# motor_ctrl_pw_v3.net
KiCad netlist of a schematic drawn in EAGLE
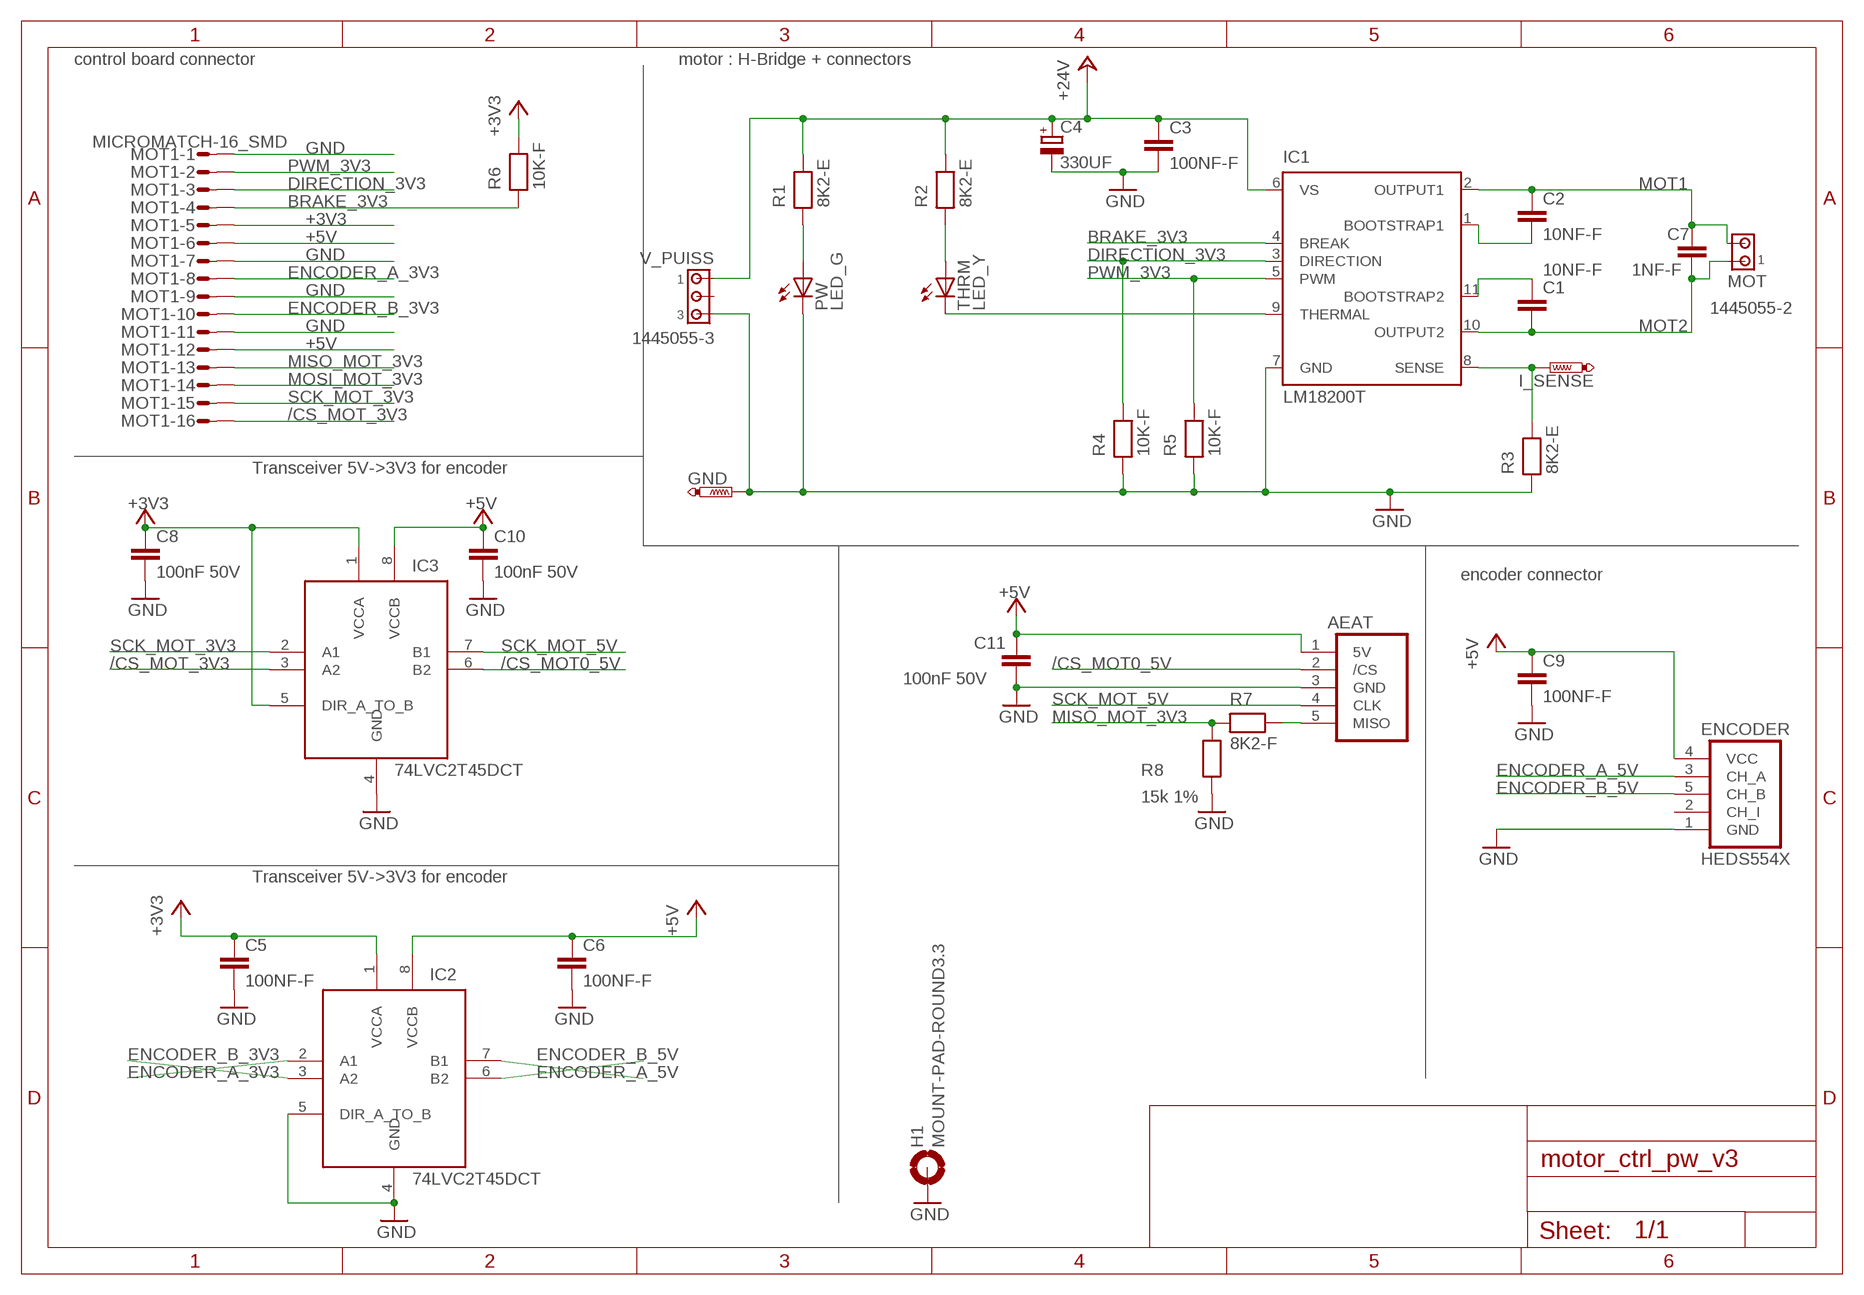
[diagram p0: schematic, sheet 1]

(export (version "E")
  (design (tool "Eeschema 10.0.6"))
  (components
    (comp (ref "AEAT")
      (value "AEAT-601X")
      (footprint "eagle-import:53047-05")
      (libsource (lib "eagle-import") (part "AEAT-601X"))
    )
    (comp (ref "C1")
      (value "10NF-F")
      (footprint "eagle-import:C0603")
      (libsource (lib "eagle-import") (part "10NF-F"))
    )
    (comp (ref "C2")
      (value "10NF-F")
      (footprint "eagle-import:C0603")
      (libsource (lib "eagle-import") (part "10NF-F"))
    )
    (comp (ref "C3")
      (value "100NF-F")
      (footprint "eagle-import:C0603")
      (libsource (lib "eagle-import") (part "100NF-F"))
    )
    (comp (ref "C4")
      (value "330UF")
      (footprint "eagle-import:PANASONIC_G")
      (fields (field (name "MANUFACTURER") "EEEFK1V331P"))
      (libsource (lib "eagle-import") (part "330UF"))
    )
    (comp (ref "C5")
      (value "100NF-F")
      (footprint "eagle-import:C0603")
      (libsource (lib "eagle-import") (part "100NF-F"))
    )
    (comp (ref "C6")
      (value "100NF-F")
      (footprint "eagle-import:C0603")
      (libsource (lib "eagle-import") (part "100NF-F"))
    )
    (comp (ref "C7")
      (value "1NF-F")
      (footprint "eagle-import:C0603")
      (libsource (lib "eagle-import") (part "1NF-F"))
    )
    (comp (ref "C8")
      (value "100nF 50V")
      (footprint "eagle-import:C0603")
      (libsource (lib "eagle-import") (part "100NF-F"))
    )
    (comp (ref "C9")
      (value "100NF-F")
      (footprint "eagle-import:C0603")
      (libsource (lib "eagle-import") (part "100NF-F"))
    )
    (comp (ref "C10")
      (value "100nF 50V")
      (footprint "eagle-import:C0603")
      (libsource (lib "eagle-import") (part "100NF-F"))
    )
    (comp (ref "C11")
      (value "100nF 50V")
      (footprint "eagle-import:C0603")
      (libsource (lib "eagle-import") (part "100NF-F"))
    )
    (comp (ref "ENCODER")
      (value "HEDS554X")
      (footprint "eagle-import:22-05-1052")
      (libsource (lib "eagle-import") (part "HEDS554X"))
    )
    (comp (ref "GND")
      (value "PTR1PAD1-13")
      (footprint "eagle-import:P1-13")
      (libsource (lib "eagle-import") (part "PTR1PAD1-13"))
    )
    (comp (ref "H1")
      (value "MOUNT-PAD-ROUND3.3")
      (footprint "eagle-import:3,3-PAD")
      (libsource (lib "eagle-import") (part "MOUNT-PAD-ROUND3.3"))
    )
    (comp (ref "IC1")
      (value "LM18200T")
      (footprint "eagle-import:TO-220-11")
      (libsource (lib "eagle-import") (part "LM18200T"))
    )
    (comp (ref "IC2")
      (value "74LVC2T45DCT")
      (footprint "eagle-import:SSOP8")
      (libsource (lib "eagle-import") (part "74LVC2T45DCT"))
    )
    (comp (ref "IC3")
      (value "74LVC2T45DCT")
      (footprint "eagle-import:SSOP8")
      (libsource (lib "eagle-import") (part "74LVC2T45DCT"))
    )
    (comp (ref "I_SENSE")
      (value "PTR1PAD1-13")
      (footprint "eagle-import:P1-13")
      (libsource (lib "eagle-import") (part "PTR1PAD1-13"))
    )
    (comp (ref "MOT")
      (value "1445055-2")
      (footprint "eagle-import:1445055-2")
      (libsource (lib "eagle-import") (part "1445055-2"))
    )
    (comp (ref "MOT1")
      (value "MICROMATCH-16_SMD")
      (footprint "eagle-import:MICROMATCH-16_SMD")
      (libsource (lib "eagle-import") (part "MICROMATCH-16_SMD"))
    )
    (comp (ref "PW")
      (value "LED_G")
      (footprint "eagle-import:CHIP-LED0805")
      (libsource (lib "eagle-import") (part "LED_G"))
    )
    (comp (ref "R1")
      (value "8K2-E")
      (footprint "eagle-import:R0805")
      (libsource (lib "eagle-import") (part "8K2-E"))
    )
    (comp (ref "R2")
      (value "8K2-E")
      (footprint "eagle-import:R0805")
      (libsource (lib "eagle-import") (part "8K2-E"))
    )
    (comp (ref "R3")
      (value "8K2-E")
      (footprint "eagle-import:R0805")
      (libsource (lib "eagle-import") (part "8K2-E"))
    )
    (comp (ref "R4")
      (value "10K-F")
      (footprint "eagle-import:R0603")
      (libsource (lib "eagle-import") (part "10K-F"))
    )
    (comp (ref "R5")
      (value "10K-F")
      (footprint "eagle-import:R0603")
      (libsource (lib "eagle-import") (part "10K-F"))
    )
    (comp (ref "R6")
      (value "10K-F")
      (footprint "eagle-import:R0603")
      (libsource (lib "eagle-import") (part "10K-F"))
    )
    (comp (ref "R7")
      (value "8K2-F")
      (footprint "eagle-import:R0603")
      (libsource (lib "eagle-import") (part "8K2-F"))
    )
    (comp (ref "R8")
      (value "15k 1%")
      (footprint "eagle-import:R0603")
      (libsource (lib "eagle-import") (part "15K-F"))
    )
    (comp (ref "THRM")
      (value "LED_Y")
      (footprint "eagle-import:CHIP-LED0805")
      (libsource (lib "eagle-import") (part "LED_Y"))
    )
    (comp (ref "V_PUISS")
      (value "1445055-3")
      (footprint "eagle-import:1445055-3")
      (libsource (lib "eagle-import") (part "1445055-3"))
    )
  )
  (nets
    (net (code "1") (name "+3V3") (class "Default")
      (node (ref "C5") (pin "1") (pinfunction "1_1") (pintype "passive"))
      (node (ref "C8") (pin "1") (pinfunction "1_1") (pintype "passive"))
      (node (ref "IC2") (pin "1") (pinfunction "VCCA_1") (pintype "power_in"))
      (node (ref "IC3") (pin "1") (pinfunction "VCCA_1") (pintype "power_in"))
      (node (ref "IC3") (pin "5") (pinfunction "DIR_A_TO_B_5") (pintype "bidirectional"))
      (node (ref "MOT1") (pin "5") (pinfunction "S_5") (pintype "passive"))
      (node (ref "R6") (pin "2") (pinfunction "2_2") (pintype "bidirectional"))
    )
    (net (code "2") (name "+5V") (class "Default")
      (node (ref "AEAT") (pin "1") (pinfunction "5V_1") (pintype "passive"))
      (node (ref "C10") (pin "1") (pinfunction "1_1") (pintype "passive"))
      (node (ref "C11") (pin "1") (pinfunction "1_1") (pintype "passive"))
      (node (ref "C6") (pin "1") (pinfunction "1_1") (pintype "passive"))
      (node (ref "C9") (pin "1") (pinfunction "1_1") (pintype "passive"))
      (node (ref "ENCODER") (pin "4") (pinfunction "VCC_4") (pintype "passive"))
      (node (ref "IC2") (pin "8") (pinfunction "VCCB_8") (pintype "power_in"))
      (node (ref "IC3") (pin "8") (pinfunction "VCCB_8") (pintype "power_in"))
      (node (ref "MOT1") (pin "12") (pinfunction "S_12") (pintype "passive"))
      (node (ref "MOT1") (pin "6") (pinfunction "S_6") (pintype "passive"))
    )
    (net (code "3") (name "+24V") (class "Default")
      (node (ref "C3") (pin "1") (pinfunction "1_1") (pintype "passive"))
      (node (ref "C4") (pin "+") (pinfunction "+_+") (pintype "passive"))
      (node (ref "IC1") (pin "6") (pinfunction "VS_6") (pintype "power_in"))
      (node (ref "R1") (pin "2") (pinfunction "2_2") (pintype "bidirectional"))
      (node (ref "R2") (pin "2") (pinfunction "2_2") (pintype "bidirectional"))
      (node (ref "V_PUISS") (pin "1") (pinfunction "1_1") (pintype "passive"))
    )
    (net (code "4") (name "/BRAKE_3V3") (class "Default")
      (node (ref "IC1") (pin "4") (pinfunction "BREAK_4") (pintype "input"))
      (node (ref "MOT1") (pin "4") (pinfunction "S_4") (pintype "passive"))
      (node (ref "R6") (pin "1") (pinfunction "1_1") (pintype "bidirectional"))
    )
    (net (code "5") (name "/DIRECTION_3V3") (class "Default")
      (node (ref "IC1") (pin "3") (pinfunction "DIRECTION_3") (pintype "input"))
      (node (ref "MOT1") (pin "3") (pinfunction "S_3") (pintype "passive"))
      (node (ref "R4") (pin "2") (pinfunction "2_2") (pintype "bidirectional"))
    )
    (net (code "6") (name "/ENCODER_A_3V3") (class "Default")
      (node (ref "IC2") (pin "2") (pinfunction "A1_2") (pintype "bidirectional"))
      (node (ref "MOT1") (pin "8") (pinfunction "S_8") (pintype "passive"))
    )
    (net (code "7") (name "/ENCODER_A_5V") (class "Default")
      (node (ref "ENCODER") (pin "3") (pinfunction "CH_A_3") (pintype "passive"))
      (node (ref "IC2") (pin "7") (pinfunction "B1_7") (pintype "bidirectional"))
    )
    (net (code "8") (name "/ENCODER_B_3V3") (class "Default")
      (node (ref "IC2") (pin "3") (pinfunction "A2_3") (pintype "bidirectional"))
      (node (ref "MOT1") (pin "10") (pinfunction "S_10") (pintype "passive"))
    )
    (net (code "9") (name "/ENCODER_B_5V") (class "Default")
      (node (ref "ENCODER") (pin "5") (pinfunction "CH_B_5") (pintype "passive"))
      (node (ref "IC2") (pin "6") (pinfunction "B2_6") (pintype "bidirectional"))
    )
    (net (code "10") (name "/MISO_MOT_3V3") (class "Default")
      (node (ref "MOT1") (pin "13") (pinfunction "S_13") (pintype "passive"))
      (node (ref "R7") (pin "1") (pinfunction "1_1") (pintype "bidirectional"))
      (node (ref "R8") (pin "2") (pinfunction "2_2") (pintype "bidirectional"))
    )
    (net (code "11") (name "/MOSI_MOT_3V3") (class "Default")
      (node (ref "MOT1") (pin "14") (pinfunction "S_14") (pintype "passive"))
    )
    (net (code "12") (name "/MOT1") (class "Default")
      (node (ref "C2") (pin "1") (pinfunction "1_1") (pintype "passive"))
      (node (ref "C7") (pin "1") (pinfunction "1_1") (pintype "passive"))
      (node (ref "IC1") (pin "2") (pinfunction "OUTPUT1_2") (pintype "output"))
      (node (ref "MOT") (pin "2") (pinfunction "2_2") (pintype "passive"))
    )
    (net (code "13") (name "/MOT2") (class "Default")
      (node (ref "C1") (pin "2") (pinfunction "2_2") (pintype "passive"))
      (node (ref "C7") (pin "2") (pinfunction "2_2") (pintype "passive"))
      (node (ref "IC1") (pin "10") (pinfunction "OUTPUT2_10") (pintype "output"))
      (node (ref "MOT") (pin "1") (pinfunction "1_1") (pintype "passive"))
    )
    (net (code "14") (name "/PWM_3V3") (class "Default")
      (node (ref "IC1") (pin "5") (pinfunction "PWM_5") (pintype "input"))
      (node (ref "MOT1") (pin "2") (pinfunction "S_2") (pintype "passive"))
      (node (ref "R5") (pin "2") (pinfunction "2_2") (pintype "bidirectional"))
    )
    (net (code "15") (name "/SCK_MOT_3V3") (class "Default")
      (node (ref "IC3") (pin "2") (pinfunction "A1_2") (pintype "bidirectional"))
      (node (ref "MOT1") (pin "15") (pinfunction "S_15") (pintype "passive"))
    )
    (net (code "16") (name "/SCK_MOT_5V") (class "Default")
      (node (ref "AEAT") (pin "4") (pinfunction "CLK_4") (pintype "passive"))
      (node (ref "IC3") (pin "7") (pinfunction "B1_7") (pintype "bidirectional"))
    )
    (net (code "17") (name "/{slash}CS_MOT0_5V") (class "Default")
      (node (ref "AEAT") (pin "2") (pinfunction "/CS_2") (pintype "passive"))
      (node (ref "IC3") (pin "6") (pinfunction "B2_6") (pintype "bidirectional"))
    )
    (net (code "18") (name "/{slash}CS_MOT_3V3") (class "Default")
      (node (ref "IC3") (pin "3") (pinfunction "A2_3") (pintype "bidirectional"))
      (node (ref "MOT1") (pin "16") (pinfunction "S_16") (pintype "passive"))
    )
    (net (code "19") (name "GND") (class "Default")
      (node (ref "AEAT") (pin "3") (pinfunction "GND_3") (pintype "passive"))
      (node (ref "C10") (pin "2") (pinfunction "2_2") (pintype "passive"))
      (node (ref "C11") (pin "2") (pinfunction "2_2") (pintype "passive"))
      (node (ref "C3") (pin "2") (pinfunction "2_2") (pintype "passive"))
      (node (ref "C4") (pin "-") (pinfunction "-_-") (pintype "passive"))
      (node (ref "C5") (pin "2") (pinfunction "2_2") (pintype "passive"))
      (node (ref "C6") (pin "2") (pinfunction "2_2") (pintype "passive"))
      (node (ref "C8") (pin "2") (pinfunction "2_2") (pintype "passive"))
      (node (ref "C9") (pin "2") (pinfunction "2_2") (pintype "passive"))
      (node (ref "ENCODER") (pin "1") (pinfunction "GND_1") (pintype "passive"))
      (node (ref "GND") (pin "TP") (pinfunction "TP_TP") (pintype "input"))
      (node (ref "H1") (pin "B3,3") (pinfunction "MOUNT_B3,3") (pintype "passive"))
      (node (ref "IC1") (pin "7") (pinfunction "GND_7") (pintype "power_in"))
      (node (ref "IC2") (pin "4") (pinfunction "GND_4") (pintype "power_in"))
      (node (ref "IC2") (pin "5") (pinfunction "DIR_A_TO_B_5") (pintype "bidirectional"))
      (node (ref "IC3") (pin "4") (pinfunction "GND_4") (pintype "power_in"))
      (node (ref "MOT1") (pin "1") (pinfunction "S_1") (pintype "passive"))
      (node (ref "MOT1") (pin "11") (pinfunction "S_11") (pintype "passive"))
      (node (ref "MOT1") (pin "7") (pinfunction "S_7") (pintype "passive"))
      (node (ref "MOT1") (pin "9") (pinfunction "S_9") (pintype "passive"))
      (node (ref "PW") (pin "C") (pinfunction "C_C") (pintype "passive"))
      (node (ref "R3") (pin "1") (pinfunction "1_1") (pintype "bidirectional"))
      (node (ref "R4") (pin "1") (pinfunction "1_1") (pintype "bidirectional"))
      (node (ref "R5") (pin "1") (pinfunction "1_1") (pintype "bidirectional"))
      (node (ref "R8") (pin "1") (pinfunction "1_1") (pintype "bidirectional"))
      (node (ref "V_PUISS") (pin "3") (pinfunction "3_3") (pintype "passive"))
    )
    (net (code "20") (name "Net-(AEAT-MISO)") (class "Default")
      (node (ref "AEAT") (pin "5") (pinfunction "MISO_5") (pintype "passive"))
      (node (ref "R7") (pin "2") (pinfunction "2_2") (pintype "bidirectional"))
    )
    (net (code "21") (name "Net-(IC1-BOOTSTRAP1)") (class "Default")
      (node (ref "C2") (pin "2") (pinfunction "2_2") (pintype "passive"))
      (node (ref "IC1") (pin "1") (pinfunction "BOOTSTRAP1_1") (pintype "input"))
    )
    (net (code "22") (name "Net-(IC1-BOOTSTRAP2)") (class "Default")
      (node (ref "C1") (pin "1") (pinfunction "1_1") (pintype "passive"))
      (node (ref "IC1") (pin "11") (pinfunction "BOOTSTRAP2_11") (pintype "input"))
    )
    (net (code "23") (name "Net-(IC1-SENSE)") (class "Default")
      (node (ref "IC1") (pin "8") (pinfunction "SENSE_8") (pintype "output"))
      (node (ref "I_SENSE") (pin "TP") (pinfunction "TP_TP") (pintype "input"))
      (node (ref "R3") (pin "2") (pinfunction "2_2") (pintype "bidirectional"))
    )
    (net (code "24") (name "Net-(IC1-THERMAL)") (class "Default")
      (node (ref "IC1") (pin "9") (pinfunction "THERMAL_9") (pintype "output"))
      (node (ref "THRM") (pin "C") (pinfunction "C_C") (pintype "passive"))
    )
    (net (code "25") (name "Net-(PW-PadA)") (class "Default")
      (node (ref "PW") (pin "A") (pinfunction "A_A") (pintype "passive"))
      (node (ref "R1") (pin "1") (pinfunction "1_1") (pintype "bidirectional"))
    )
    (net (code "26") (name "Net-(R2-Pad1)") (class "Default")
      (node (ref "R2") (pin "1") (pinfunction "1_1") (pintype "bidirectional"))
      (node (ref "THRM") (pin "A") (pinfunction "A_A") (pintype "passive"))
    )
    (net (code "27") (name "unconnected-(ENCODER-CH_I-Pad2)") (class "Default")
      (node (ref "ENCODER") (pin "2") (pinfunction "CH_I_2") (pintype "passive"))
    )
    (net (code "28") (name "unconnected-(V_PUISS-Pad2)") (class "Default")
      (node (ref "V_PUISS") (pin "2") (pinfunction "2_2") (pintype "passive"))
    )
  )
)
